# Con_nb3000_ledkb.net
KiCad netlist of a schematic drawn in Altium Designer
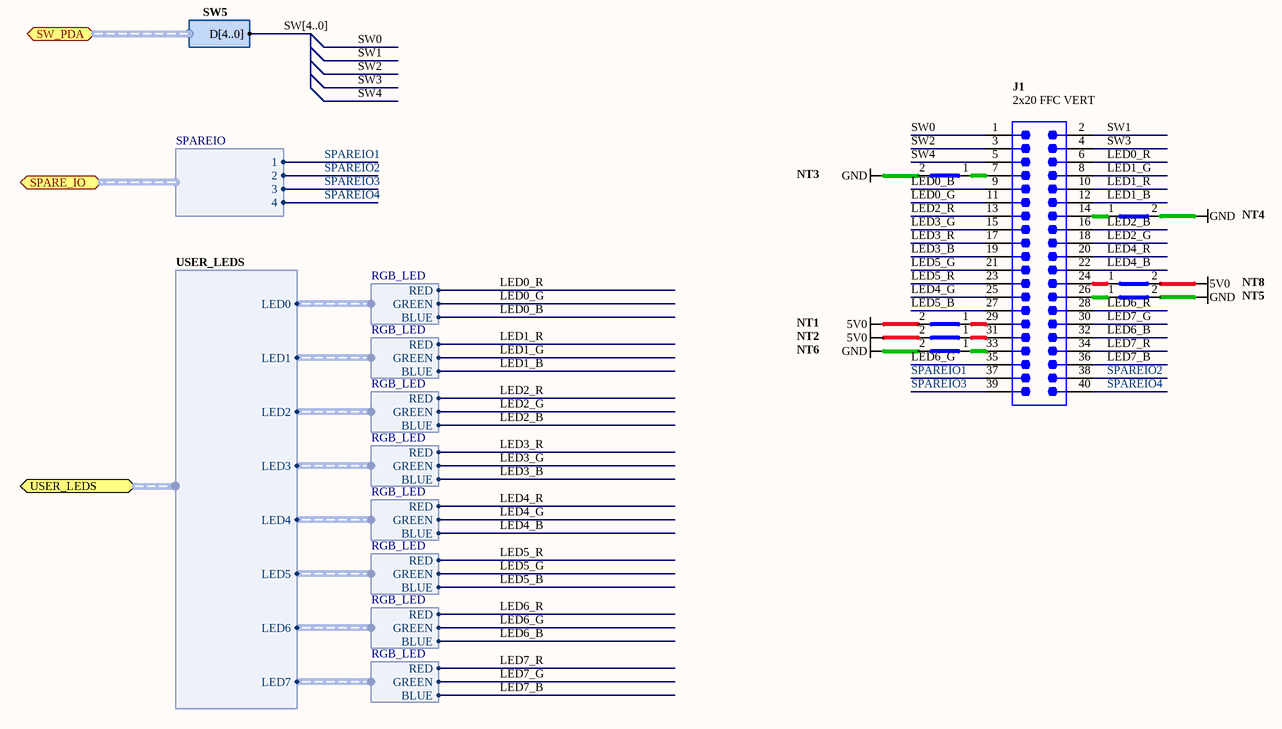
[diagram p0: Con_nb3000_ledkb.schdoc]

(export (version "E")
  (design (tool "Eeschema 10.0.6"))
  (components
    (comp (ref "J1")
      (value "2x20 FFC VERT")
      (footprint "FPC-xxS1VN3R")
      (description "Header FFC, 2x20 pin Vertical, 0.5mm")
      (libsource (lib "AltiumDesignLibrary") (part "CON-FFC-2x20-VERT"))
    )
    (comp (ref "NT1")
      (value "Net Tie SMT2")
      (footprint "NETTIE-SMT2-8X8")
      (description "Net-Tie, Surface Mount, 2 x 1.6mm x 0.8mm SMT Pads - For 0.8mm Track")
      (libsource (lib "AltiumDesignLibrary") (part "NETTIE-SMT2"))
    )
    (comp (ref "NT2")
      (value "Net Tie SMT2")
      (footprint "NETTIE-SMT2-8X8")
      (description "Net-Tie, Surface Mount, 2 x 1.6mm x 0.8mm SMT Pads - For 0.8mm Track")
      (libsource (lib "AltiumDesignLibrary") (part "NETTIE-SMT2"))
    )
    (comp (ref "NT3")
      (value "Net Tie SMT2")
      (footprint "NETTIE-SMT2-8X8")
      (description "Net-Tie, Surface Mount, 2 x 1.6mm x 0.8mm SMT Pads - For 0.8mm Track")
      (libsource (lib "AltiumDesignLibrary") (part "NETTIE-SMT2"))
    )
    (comp (ref "NT4")
      (value "Net Tie SMT2")
      (footprint "NETTIE-SMT2-8X8")
      (description "Net-Tie, Surface Mount, 2 x 1.6mm x 0.8mm SMT Pads - For 0.8mm Track")
      (libsource (lib "AltiumDesignLibrary") (part "NETTIE-SMT2"))
    )
    (comp (ref "NT5")
      (value "Net Tie SMT2")
      (footprint "NETTIE-SMT2-8X8")
      (description "Net-Tie, Surface Mount, 2 x 1.6mm x 0.8mm SMT Pads - For 0.8mm Track")
      (libsource (lib "AltiumDesignLibrary") (part "NETTIE-SMT2"))
    )
    (comp (ref "NT6")
      (value "Net Tie SMT2")
      (footprint "NETTIE-SMT2-8X8")
      (description "Net-Tie, Surface Mount, 2 x 1.6mm x 0.8mm SMT Pads - For 0.8mm Track")
      (libsource (lib "AltiumDesignLibrary") (part "NETTIE-SMT2"))
    )
    (comp (ref "NT8")
      (value "Net Tie SMT2")
      (footprint "NETTIE-SMT2-8X8")
      (description "Net-Tie, Surface Mount, 2 x 1.6mm x 0.8mm SMT Pads - For 0.8mm Track")
      (libsource (lib "AltiumDesignLibrary") (part "NETTIE-SMT2"))
    )
  )
  (nets
    (net (code "6") (name "/LED0_B") (class "Default")
      (node (ref "J1") (pin "9") (pinfunction "9_9") (pintype "passive"))
    )
    (net (code "7") (name "/LED0_G") (class "Default")
      (node (ref "J1") (pin "11") (pinfunction "11_11") (pintype "passive"))
    )
    (net (code "8") (name "/LED0_R") (class "Default")
      (node (ref "J1") (pin "6") (pinfunction "6_6") (pintype "passive"))
    )
    (net (code "9") (name "/LED1_B") (class "Default")
      (node (ref "J1") (pin "12") (pinfunction "12_12") (pintype "passive"))
    )
    (net (code "10") (name "/LED1_G") (class "Default")
      (node (ref "J1") (pin "8") (pinfunction "8_8") (pintype "passive"))
    )
    (net (code "11") (name "/LED1_R") (class "Default")
      (node (ref "J1") (pin "10") (pinfunction "10_10") (pintype "passive"))
    )
    (net (code "12") (name "/LED2_B") (class "Default")
      (node (ref "J1") (pin "16") (pinfunction "16_16") (pintype "passive"))
    )
    (net (code "13") (name "/LED2_G") (class "Default")
      (node (ref "J1") (pin "18") (pinfunction "18_18") (pintype "passive"))
    )
    (net (code "14") (name "/LED2_R") (class "Default")
      (node (ref "J1") (pin "13") (pinfunction "13_13") (pintype "passive"))
    )
    (net (code "15") (name "/LED3_B") (class "Default")
      (node (ref "J1") (pin "19") (pinfunction "19_19") (pintype "passive"))
    )
    (net (code "16") (name "/LED3_G") (class "Default")
      (node (ref "J1") (pin "15") (pinfunction "15_15") (pintype "passive"))
    )
    (net (code "17") (name "/LED3_R") (class "Default")
      (node (ref "J1") (pin "17") (pinfunction "17_17") (pintype "passive"))
    )
    (net (code "18") (name "/LED4_B") (class "Default")
      (node (ref "J1") (pin "22") (pinfunction "22_22") (pintype "passive"))
    )
    (net (code "19") (name "/LED4_G") (class "Default")
      (node (ref "J1") (pin "25") (pinfunction "25_25") (pintype "passive"))
    )
    (net (code "20") (name "/LED4_R") (class "Default")
      (node (ref "J1") (pin "20") (pinfunction "20_20") (pintype "passive"))
    )
    (net (code "21") (name "/LED5_B") (class "Default")
      (node (ref "J1") (pin "27") (pinfunction "27_27") (pintype "passive"))
    )
    (net (code "22") (name "/LED5_G") (class "Default")
      (node (ref "J1") (pin "21") (pinfunction "21_21") (pintype "passive"))
    )
    (net (code "23") (name "/LED5_R") (class "Default")
      (node (ref "J1") (pin "23") (pinfunction "23_23") (pintype "passive"))
    )
    (net (code "24") (name "/LED6_B") (class "Default")
      (node (ref "J1") (pin "32") (pinfunction "32_32") (pintype "passive"))
    )
    (net (code "25") (name "/LED6_G") (class "Default")
      (node (ref "J1") (pin "35") (pinfunction "35_35") (pintype "passive"))
    )
    (net (code "26") (name "/LED6_R") (class "Default")
      (node (ref "J1") (pin "28") (pinfunction "28_28") (pintype "passive"))
    )
    (net (code "27") (name "/LED7_B") (class "Default")
      (node (ref "J1") (pin "36") (pinfunction "36_36") (pintype "passive"))
    )
    (net (code "28") (name "/LED7_G") (class "Default")
      (node (ref "J1") (pin "30") (pinfunction "30_30") (pintype "passive"))
    )
    (net (code "29") (name "/LED7_R") (class "Default")
      (node (ref "J1") (pin "34") (pinfunction "34_34") (pintype "passive"))
    )
    (net (code "30") (name "/SPAREIO1") (class "Default")
      (node (ref "J1") (pin "37") (pinfunction "37_37") (pintype "passive"))
    )
    (net (code "31") (name "/SPAREIO2") (class "Default")
      (node (ref "J1") (pin "38") (pinfunction "38_38") (pintype "passive"))
    )
    (net (code "32") (name "/SPAREIO3") (class "Default")
      (node (ref "J1") (pin "39") (pinfunction "39_39") (pintype "passive"))
    )
    (net (code "33") (name "/SPAREIO4") (class "Default")
      (node (ref "J1") (pin "40") (pinfunction "40_40") (pintype "passive"))
    )
    (net (code "34") (name "/SW0") (class "Default")
      (node (ref "J1") (pin "1") (pinfunction "1_1") (pintype "passive"))
    )
    (net (code "35") (name "/SW1") (class "Default")
      (node (ref "J1") (pin "2") (pinfunction "2_2") (pintype "passive"))
    )
    (net (code "36") (name "/SW2") (class "Default")
      (node (ref "J1") (pin "3") (pinfunction "3_3") (pintype "passive"))
    )
    (net (code "37") (name "/SW3") (class "Default")
      (node (ref "J1") (pin "4") (pinfunction "4_4") (pintype "passive"))
    )
    (net (code "38") (name "/SW4") (class "Default")
      (node (ref "J1") (pin "5") (pinfunction "5_5") (pintype "passive"))
    )
    (net (code "45") (name "5V0") (class "Default")
      (node (ref "NT1") (pin "2") (pinfunction "Net2_2") (pintype "passive"))
      (node (ref "NT2") (pin "2") (pinfunction "Net2_2") (pintype "passive"))
      (node (ref "NT8") (pin "2") (pinfunction "Net2_2") (pintype "passive"))
    )
    (net (code "46") (name "GND") (class "Default")
      (node (ref "NT3") (pin "2") (pinfunction "Net2_2") (pintype "passive"))
      (node (ref "NT4") (pin "2") (pinfunction "Net2_2") (pintype "passive"))
      (node (ref "NT5") (pin "2") (pinfunction "Net2_2") (pintype "passive"))
      (node (ref "NT6") (pin "2") (pinfunction "Net2_2") (pintype "passive"))
    )
    (net (code "47") (name "Net-(NT1-Net1)") (class "Default")
      (node (ref "J1") (pin "29") (pinfunction "29_29") (pintype "passive"))
      (node (ref "NT1") (pin "1") (pinfunction "Net1_1") (pintype "passive"))
    )
    (net (code "48") (name "Net-(NT2-Net1)") (class "Default")
      (node (ref "J1") (pin "31") (pinfunction "31_31") (pintype "passive"))
      (node (ref "NT2") (pin "1") (pinfunction "Net1_1") (pintype "passive"))
    )
    (net (code "49") (name "Net-(NT3-Net1)") (class "Default")
      (node (ref "J1") (pin "7") (pinfunction "7_7") (pintype "passive"))
      (node (ref "NT3") (pin "1") (pinfunction "Net1_1") (pintype "passive"))
    )
    (net (code "50") (name "Net-(NT4-Net1)") (class "Default")
      (node (ref "J1") (pin "14") (pinfunction "14_14") (pintype "passive"))
      (node (ref "NT4") (pin "1") (pinfunction "Net1_1") (pintype "passive"))
    )
    (net (code "51") (name "Net-(NT5-Net1)") (class "Default")
      (node (ref "J1") (pin "26") (pinfunction "26_26") (pintype "passive"))
      (node (ref "NT5") (pin "1") (pinfunction "Net1_1") (pintype "passive"))
    )
    (net (code "52") (name "Net-(NT6-Net1)") (class "Default")
      (node (ref "J1") (pin "33") (pinfunction "33_33") (pintype "passive"))
      (node (ref "NT6") (pin "1") (pinfunction "Net1_1") (pintype "passive"))
    )
    (net (code "53") (name "Net-(NT8-Net1)") (class "Default")
      (node (ref "J1") (pin "24") (pinfunction "24_24") (pintype "passive"))
      (node (ref "NT8") (pin "1") (pinfunction "Net1_1") (pintype "passive"))
    )
  )
)
